# LVDS.net
KiCad netlist of a schematic drawn in Altium Designer
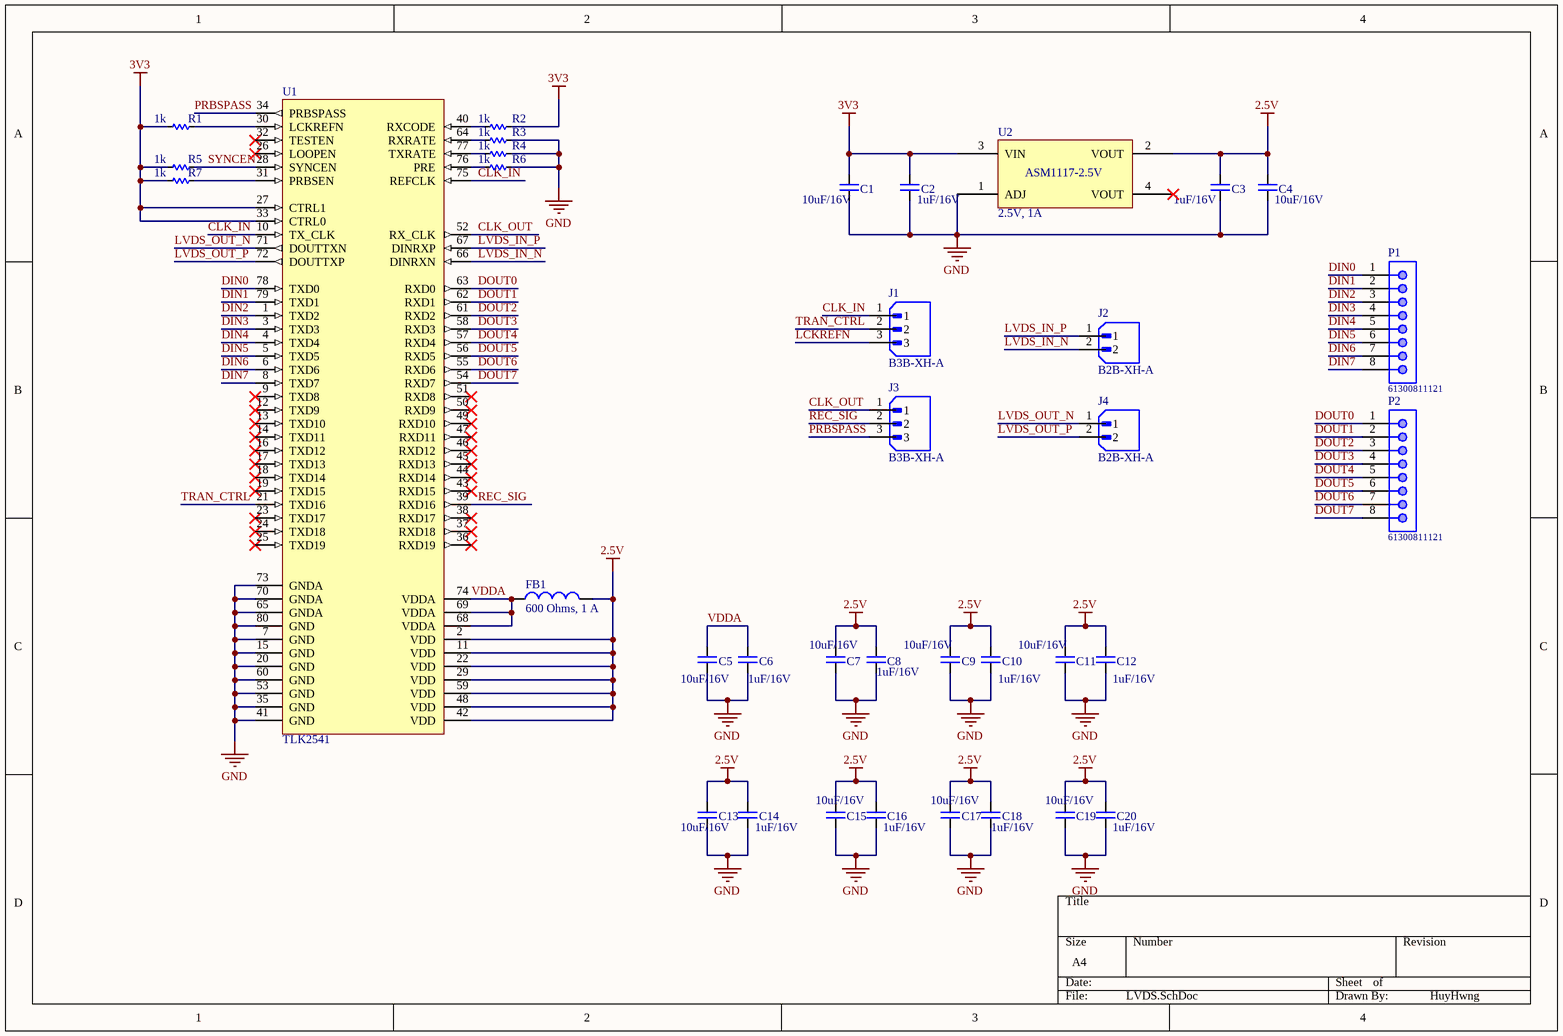
[diagram p0: LVDS.SchDoc]

(export (version "E")
  (design (tool "Eeschema 10.0.6"))
  (components
    (comp (ref "C1")
      (value "10uF/16V")
      (footprint "CAP_C_1608X80")
      (description "CAP_Chip")
      (libsource (lib "LABLIB") (part "CAP_SMD"))
    )
    (comp (ref "C2")
      (value "1uF/16V")
      (footprint "CAP_C_1608X80")
      (description "CAP_Chip")
      (libsource (lib "LABLIB") (part "CAP_SMD"))
    )
    (comp (ref "C3")
      (value "1uF/16V")
      (footprint "CAP_C_1608X80")
      (description "CAP_Chip")
      (libsource (lib "LABLIB") (part "CAP_SMD"))
    )
    (comp (ref "C4")
      (value "10uF/16V")
      (footprint "CAP_C_1608X80")
      (description "CAP_Chip")
      (libsource (lib "LABLIB") (part "CAP_SMD"))
    )
    (comp (ref "C5")
      (value "10uF/16V")
      (footprint "CAP_C_1608X80")
      (description "CAP_Chip")
      (libsource (lib "LABLIB") (part "CAP_SMD"))
    )
    (comp (ref "C6")
      (value "1uF/16V")
      (footprint "CAP_C_1608X80")
      (description "CAP_Chip")
      (libsource (lib "LABLIB") (part "CAP_SMD"))
    )
    (comp (ref "C7")
      (value "10uF/16V")
      (footprint "CAP_C_1608X80")
      (description "CAP_Chip")
      (libsource (lib "LABLIB") (part "CAP_SMD"))
    )
    (comp (ref "C8")
      (value "1uF/16V")
      (footprint "CAP_C_1608X80")
      (description "CAP_Chip")
      (libsource (lib "LABLIB") (part "CAP_SMD"))
    )
    (comp (ref "C9")
      (value "10uF/16V")
      (footprint "CAP_C_1608X80")
      (description "CAP_Chip")
      (libsource (lib "LABLIB") (part "CAP_SMD"))
    )
    (comp (ref "C10")
      (value "1uF/16V")
      (footprint "CAP_C_1608X80")
      (description "CAP_Chip")
      (libsource (lib "LABLIB") (part "CAP_SMD"))
    )
    (comp (ref "C11")
      (value "10uF/16V")
      (footprint "CAP_C_1608X80")
      (description "CAP_Chip")
      (libsource (lib "LABLIB") (part "CAP_SMD"))
    )
    (comp (ref "C12")
      (value "1uF/16V")
      (footprint "CAP_C_1608X80")
      (description "CAP_Chip")
      (libsource (lib "LABLIB") (part "CAP_SMD"))
    )
    (comp (ref "C13")
      (value "10uF/16V")
      (footprint "CAP_C_1608X80")
      (description "CAP_Chip")
      (libsource (lib "LABLIB") (part "CAP_SMD"))
    )
    (comp (ref "C14")
      (value "1uF/16V")
      (footprint "CAP_C_1608X80")
      (description "CAP_Chip")
      (libsource (lib "LABLIB") (part "CAP_SMD"))
    )
    (comp (ref "C15")
      (value "10uF/16V")
      (footprint "CAP_C_1608X80")
      (description "CAP_Chip")
      (libsource (lib "LABLIB") (part "CAP_SMD"))
    )
    (comp (ref "C16")
      (value "1uF/16V")
      (footprint "CAP_C_1608X80")
      (description "CAP_Chip")
      (libsource (lib "LABLIB") (part "CAP_SMD"))
    )
    (comp (ref "C17")
      (value "10uF/16V")
      (footprint "CAP_C_1608X80")
      (description "CAP_Chip")
      (libsource (lib "LABLIB") (part "CAP_SMD"))
    )
    (comp (ref "C18")
      (value "1uF/16V")
      (footprint "CAP_C_1608X80")
      (description "CAP_Chip")
      (libsource (lib "LABLIB") (part "CAP_SMD"))
    )
    (comp (ref "C19")
      (value "10uF/16V")
      (footprint "CAP_C_1608X80")
      (description "CAP_Chip")
      (libsource (lib "LABLIB") (part "CAP_SMD"))
    )
    (comp (ref "C20")
      (value "1uF/16V")
      (footprint "CAP_C_1608X80")
      (description "CAP_Chip")
      (libsource (lib "LABLIB") (part "CAP_SMD"))
    )
    (comp (ref "FB1")
      (value "600 Ohms, 1 A")
      (footprint "FER_0603")
      (description "Ferrite, 0603, 600 Ohms, 1 A")
      (fields (field (name "TOLERANCE") "+/-25%"))
      (libsource (lib "Altium_Ferrite_Bead") (part "03060360110225"))
    )
    (comp (ref "J1")
      (value "B3B-XH-A")
      (footprint "JST_B3B-XH-A")
      (description "Connector Header Through Hole 3 position 0.098 (2.50mm)")
      (fields (field (name "MF") "JST Sales"))
      (libsource (lib "B3B-XH-A") (part "B3B-XH-A"))
    )
    (comp (ref "J2")
      (value "B2B-XH-A")
      (footprint "JST_B2B-XH-A")
      (fields (field (name "MF") "{'manufacturer': u'JST Sales America Inc.'}"))
      (libsource (lib "B2B-XH-A") (part "B2B-XH-A"))
    )
    (comp (ref "J3")
      (value "B3B-XH-A")
      (footprint "JST_B3B-XH-A")
      (description "Connector Header Through Hole 3 position 0.098 (2.50mm)")
      (fields (field (name "MF") "JST Sales"))
      (libsource (lib "B3B-XH-A") (part "B3B-XH-A"))
    )
    (comp (ref "J4")
      (value "B2B-XH-A")
      (footprint "JST_B2B-XH-A")
      (fields (field (name "MF") "{'manufacturer': u'JST Sales America Inc.'}"))
      (libsource (lib "B2B-XH-A") (part "B2B-XH-A"))
    )
    (comp (ref "P1")
      (value "61300811121")
      (footprint "61300811121")
      (description "WR-PHD Pin Header, THT, pitch 2.54mm, Single Row, Vertical, 8p")
      (fields (field (name "MANUFACTURER") "Wurth Elektronik"))
      (libsource (lib "Altium_Header") (part "61300811121"))
    )
    (comp (ref "P2")
      (value "61300811121")
      (footprint "61300811121")
      (description "WR-PHD Pin Header, THT, pitch 2.54mm, Single Row, Vertical, 8p")
      (fields (field (name "MANUFACTURER") "Wurth Elektronik"))
      (libsource (lib "Altium_Header") (part "61300811121"))
    )
    (comp (ref "R1")
      (value "1k")
      (footprint "RES_C_1608X60")
      (description "RES")
      (libsource (lib "LABLIB") (part "_RES_B_2"))
    )
    (comp (ref "R2")
      (value "1k")
      (footprint "RES_C_1608X60")
      (description "RES")
      (libsource (lib "LABLIB") (part "_RES_B_2"))
    )
    (comp (ref "R3")
      (value "1k")
      (footprint "RES_C_1608X60")
      (description "RES")
      (libsource (lib "LABLIB") (part "_RES_B_2"))
    )
    (comp (ref "R4")
      (value "1k")
      (footprint "RES_C_1608X60")
      (description "RES")
      (libsource (lib "LABLIB") (part "_RES_B_2"))
    )
    (comp (ref "R5")
      (value "1k")
      (footprint "RES_C_1608X60")
      (description "RES")
      (libsource (lib "LABLIB") (part "_RES_B_2"))
    )
    (comp (ref "R6")
      (value "1k")
      (footprint "RES_C_1608X60")
      (description "RES")
      (libsource (lib "LABLIB") (part "_RES_B_2"))
    )
    (comp (ref "R7")
      (value "1k")
      (footprint "RES_C_1608X60")
      (description "RES")
      (libsource (lib "LABLIB") (part "_RES_B_2"))
    )
    (comp (ref "U1")
      (value "TLK2541")
      (footprint "TLK2541")
      (description "1 TO2.6 GBPS TRANSCEIVER")
      (libsource (lib "3_HuyHung") (part "TLK2541"))
    )
    (comp (ref "U2")
      (value "2.5V, 1A")
      (footprint "AMS1117-2.5V SOT223")
      (description "AMS1117-2.5V, OUT 2.5V 1A.")
      (fields (field (name "MANUFACTURER") "AMS"))
      (libsource (lib "Altium_Power_Supply_IC") (part "AMS1117-2.5V"))
    )
  )
  (nets
    (net (code "1") (name "/CLK_IN") (class "Default")
      (node (ref "J1") (pin "1") (pinfunction "1_1") (pintype "passive"))
      (node (ref "U1") (pin "10") (pinfunction "TX_CLK_10") (pintype "input"))
      (node (ref "U1") (pin "75") (pinfunction "REFCLK_75") (pintype "input"))
    )
    (net (code "2") (name "/CLK_OUT") (class "Default")
      (node (ref "J3") (pin "1") (pinfunction "1_1") (pintype "passive"))
      (node (ref "U1") (pin "52") (pinfunction "RX_CLK_52") (pintype "output"))
    )
    (net (code "3") (name "/DIN0") (class "Default")
      (node (ref "P1") (pin "1") (pinfunction "1_1") (pintype "passive"))
      (node (ref "U1") (pin "78") (pinfunction "TXD0_78") (pintype "input"))
    )
    (net (code "4") (name "/DIN1") (class "Default")
      (node (ref "P1") (pin "2") (pinfunction "2_2") (pintype "passive"))
      (node (ref "U1") (pin "79") (pinfunction "TXD1_79") (pintype "input"))
    )
    (net (code "5") (name "/DIN2") (class "Default")
      (node (ref "P1") (pin "3") (pinfunction "3_3") (pintype "passive"))
      (node (ref "U1") (pin "1") (pinfunction "TXD2_1") (pintype "input"))
    )
    (net (code "6") (name "/DIN3") (class "Default")
      (node (ref "P1") (pin "4") (pinfunction "4_4") (pintype "passive"))
      (node (ref "U1") (pin "3") (pinfunction "TXD3_3") (pintype "input"))
    )
    (net (code "7") (name "/DIN4") (class "Default")
      (node (ref "P1") (pin "5") (pinfunction "5_5") (pintype "passive"))
      (node (ref "U1") (pin "4") (pinfunction "TXD4_4") (pintype "input"))
    )
    (net (code "8") (name "/DIN5") (class "Default")
      (node (ref "P1") (pin "6") (pinfunction "6_6") (pintype "passive"))
      (node (ref "U1") (pin "5") (pinfunction "TXD5_5") (pintype "input"))
    )
    (net (code "9") (name "/DIN6") (class "Default")
      (node (ref "P1") (pin "7") (pinfunction "7_7") (pintype "passive"))
      (node (ref "U1") (pin "6") (pinfunction "TXD6_6") (pintype "input"))
    )
    (net (code "10") (name "/DIN7") (class "Default")
      (node (ref "P1") (pin "8") (pinfunction "8_8") (pintype "passive"))
      (node (ref "U1") (pin "8") (pinfunction "TXD7_8") (pintype "input"))
    )
    (net (code "11") (name "/DOUT0") (class "Default")
      (node (ref "P2") (pin "1") (pinfunction "1_1") (pintype "passive"))
      (node (ref "U1") (pin "63") (pinfunction "RXD0_63") (pintype "output"))
    )
    (net (code "12") (name "/DOUT1") (class "Default")
      (node (ref "P2") (pin "2") (pinfunction "2_2") (pintype "passive"))
      (node (ref "U1") (pin "62") (pinfunction "RXD1_62") (pintype "output"))
    )
    (net (code "13") (name "/DOUT2") (class "Default")
      (node (ref "P2") (pin "3") (pinfunction "3_3") (pintype "passive"))
      (node (ref "U1") (pin "61") (pinfunction "RXD2_61") (pintype "output"))
    )
    (net (code "14") (name "/DOUT3") (class "Default")
      (node (ref "P2") (pin "4") (pinfunction "4_4") (pintype "passive"))
      (node (ref "U1") (pin "58") (pinfunction "RXD3_58") (pintype "output"))
    )
    (net (code "15") (name "/DOUT4") (class "Default")
      (node (ref "P2") (pin "5") (pinfunction "5_5") (pintype "passive"))
      (node (ref "U1") (pin "57") (pinfunction "RXD4_57") (pintype "output"))
    )
    (net (code "16") (name "/DOUT5") (class "Default")
      (node (ref "P2") (pin "6") (pinfunction "6_6") (pintype "passive"))
      (node (ref "U1") (pin "56") (pinfunction "RXD5_56") (pintype "output"))
    )
    (net (code "17") (name "/DOUT6") (class "Default")
      (node (ref "P2") (pin "7") (pinfunction "7_7") (pintype "passive"))
      (node (ref "U1") (pin "55") (pinfunction "RXD6_55") (pintype "output"))
    )
    (net (code "18") (name "/DOUT7") (class "Default")
      (node (ref "P2") (pin "8") (pinfunction "8_8") (pintype "passive"))
      (node (ref "U1") (pin "54") (pinfunction "RXD7_54") (pintype "output"))
    )
    (net (code "19") (name "/LCKREFN") (class "Default")
      (node (ref "J1") (pin "3") (pinfunction "3_3") (pintype "passive"))
    )
    (net (code "20") (name "/LVDS_IN_N") (class "Default")
      (node (ref "J2") (pin "2") (pinfunction "2_2") (pintype "passive"))
      (node (ref "U1") (pin "66") (pinfunction "DINRXN_66") (pintype "input"))
    )
    (net (code "21") (name "/LVDS_IN_P") (class "Default")
      (node (ref "J2") (pin "1") (pinfunction "1_1") (pintype "passive"))
      (node (ref "U1") (pin "67") (pinfunction "DINRXP_67") (pintype "input"))
    )
    (net (code "22") (name "/LVDS_OUT_N") (class "Default")
      (node (ref "J4") (pin "1") (pinfunction "1_1") (pintype "passive"))
      (node (ref "U1") (pin "71") (pinfunction "DOUTTXN_71") (pintype "output"))
    )
    (net (code "23") (name "/LVDS_OUT_P") (class "Default")
      (node (ref "J4") (pin "2") (pinfunction "2_2") (pintype "passive"))
      (node (ref "U1") (pin "72") (pinfunction "DOUTTXP_72") (pintype "output"))
    )
    (net (code "24") (name "/PRBSPASS") (class "Default")
      (node (ref "J3") (pin "3") (pinfunction "3_3") (pintype "passive"))
      (node (ref "U1") (pin "34") (pinfunction "PRBSPASS_34") (pintype "output"))
    )
    (net (code "25") (name "/REC_SIG") (class "Default")
      (node (ref "J3") (pin "2") (pinfunction "2_2") (pintype "passive"))
      (node (ref "U1") (pin "39") (pinfunction "RXD16_39") (pintype "output"))
    )
    (net (code "26") (name "/SYNCEN") (class "Default")
      (node (ref "R5") (pin "1") (pinfunction "1_1") (pintype "passive"))
      (node (ref "U1") (pin "28") (pinfunction "SYNCEN_28") (pintype "input"))
    )
    (net (code "27") (name "/TRAN_CTRL") (class "Default")
      (node (ref "J1") (pin "2") (pinfunction "2_2") (pintype "passive"))
      (node (ref "U1") (pin "21") (pinfunction "TXD16_21") (pintype "input"))
    )
    (net (code "28") (name "/VDDA") (class "Default")
      (node (ref "C5") (pin "2") (pinfunction "2_2") (pintype "passive"))
      (node (ref "C6") (pin "2") (pinfunction "2_2") (pintype "passive"))
      (node (ref "FB1") (pin "1") (pinfunction "1_1") (pintype "passive"))
      (node (ref "U1") (pin "68") (pinfunction "VDDA_68") (pintype "power_in"))
      (node (ref "U1") (pin "69") (pinfunction "VDDA_69") (pintype "power_in"))
      (node (ref "U1") (pin "74") (pinfunction "VDDA_74") (pintype "power_in"))
    )
    (net (code "29") (name "2.5V") (class "Default")
      (node (ref "C10") (pin "2") (pinfunction "2_2") (pintype "passive"))
      (node (ref "C11") (pin "2") (pinfunction "2_2") (pintype "passive"))
      (node (ref "C12") (pin "2") (pinfunction "2_2") (pintype "passive"))
      (node (ref "C13") (pin "2") (pinfunction "2_2") (pintype "passive"))
      (node (ref "C14") (pin "2") (pinfunction "2_2") (pintype "passive"))
      (node (ref "C15") (pin "2") (pinfunction "2_2") (pintype "passive"))
      (node (ref "C16") (pin "2") (pinfunction "2_2") (pintype "passive"))
      (node (ref "C17") (pin "2") (pinfunction "2_2") (pintype "passive"))
      (node (ref "C18") (pin "2") (pinfunction "2_2") (pintype "passive"))
      (node (ref "C19") (pin "2") (pinfunction "2_2") (pintype "passive"))
      (node (ref "C20") (pin "2") (pinfunction "2_2") (pintype "passive"))
      (node (ref "C3") (pin "2") (pinfunction "2_2") (pintype "passive"))
      (node (ref "C4") (pin "2") (pinfunction "2_2") (pintype "passive"))
      (node (ref "C7") (pin "2") (pinfunction "2_2") (pintype "passive"))
      (node (ref "C8") (pin "2") (pinfunction "2_2") (pintype "passive"))
      (node (ref "C9") (pin "2") (pinfunction "2_2") (pintype "passive"))
      (node (ref "FB1") (pin "2") (pinfunction "2_2") (pintype "passive"))
      (node (ref "U1") (pin "11") (pinfunction "VDD_11") (pintype "power_in"))
      (node (ref "U1") (pin "2") (pinfunction "VDD_2") (pintype "power_in"))
      (node (ref "U1") (pin "22") (pinfunction "VDD_22") (pintype "power_in"))
      (node (ref "U1") (pin "29") (pinfunction "VDD_29") (pintype "power_in"))
      (node (ref "U1") (pin "42") (pinfunction "VDD_42") (pintype "power_in"))
      (node (ref "U1") (pin "48") (pinfunction "VDD_48") (pintype "power_in"))
      (node (ref "U1") (pin "59") (pinfunction "VDD_59") (pintype "power_in"))
      (node (ref "U2") (pin "2") (pinfunction "VOUT_2") (pintype "passive"))
    )
    (net (code "30") (name "3V3") (class "Default")
      (node (ref "C1") (pin "2") (pinfunction "2_2") (pintype "passive"))
      (node (ref "C2") (pin "2") (pinfunction "2_2") (pintype "passive"))
      (node (ref "R1") (pin "2") (pinfunction "2_2") (pintype "passive"))
      (node (ref "R2") (pin "1") (pinfunction "1_1") (pintype "passive"))
      (node (ref "R5") (pin "2") (pinfunction "2_2") (pintype "passive"))
      (node (ref "R7") (pin "2") (pinfunction "2_2") (pintype "passive"))
      (node (ref "U1") (pin "27") (pinfunction "CTRL1_27") (pintype "input"))
      (node (ref "U1") (pin "33") (pinfunction "CTRL0_33") (pintype "input"))
      (node (ref "U2") (pin "3") (pinfunction "VIN_3") (pintype "passive"))
    )
    (net (code "31") (name "GND") (class "Default")
      (node (ref "C1") (pin "1") (pinfunction "1_1") (pintype "passive"))
      (node (ref "C10") (pin "1") (pinfunction "1_1") (pintype "passive"))
      (node (ref "C11") (pin "1") (pinfunction "1_1") (pintype "passive"))
      (node (ref "C12") (pin "1") (pinfunction "1_1") (pintype "passive"))
      (node (ref "C13") (pin "1") (pinfunction "1_1") (pintype "passive"))
      (node (ref "C14") (pin "1") (pinfunction "1_1") (pintype "passive"))
      (node (ref "C15") (pin "1") (pinfunction "1_1") (pintype "passive"))
      (node (ref "C16") (pin "1") (pinfunction "1_1") (pintype "passive"))
      (node (ref "C17") (pin "1") (pinfunction "1_1") (pintype "passive"))
      (node (ref "C18") (pin "1") (pinfunction "1_1") (pintype "passive"))
      (node (ref "C19") (pin "1") (pinfunction "1_1") (pintype "passive"))
      (node (ref "C2") (pin "1") (pinfunction "1_1") (pintype "passive"))
      (node (ref "C20") (pin "1") (pinfunction "1_1") (pintype "passive"))
      (node (ref "C3") (pin "1") (pinfunction "1_1") (pintype "passive"))
      (node (ref "C4") (pin "1") (pinfunction "1_1") (pintype "passive"))
      (node (ref "C5") (pin "1") (pinfunction "1_1") (pintype "passive"))
      (node (ref "C6") (pin "1") (pinfunction "1_1") (pintype "passive"))
      (node (ref "C7") (pin "1") (pinfunction "1_1") (pintype "passive"))
      (node (ref "C8") (pin "1") (pinfunction "1_1") (pintype "passive"))
      (node (ref "C9") (pin "1") (pinfunction "1_1") (pintype "passive"))
      (node (ref "R3") (pin "1") (pinfunction "1_1") (pintype "passive"))
      (node (ref "R4") (pin "1") (pinfunction "1_1") (pintype "passive"))
      (node (ref "R6") (pin "1") (pinfunction "1_1") (pintype "passive"))
      (node (ref "U1") (pin "15") (pinfunction "GND_15") (pintype "power_in"))
      (node (ref "U1") (pin "20") (pinfunction "GND_20") (pintype "power_in"))
      (node (ref "U1") (pin "35") (pinfunction "GND_35") (pintype "power_in"))
      (node (ref "U1") (pin "41") (pinfunction "GND_41") (pintype "power_in"))
      (node (ref "U1") (pin "53") (pinfunction "GND_53") (pintype "power_in"))
      (node (ref "U1") (pin "60") (pinfunction "GND_60") (pintype "power_in"))
      (node (ref "U1") (pin "65") (pinfunction "GNDA_65") (pintype "power_in"))
      (node (ref "U1") (pin "7") (pinfunction "GND_7") (pintype "power_in"))
      (node (ref "U1") (pin "70") (pinfunction "GNDA_70") (pintype "power_in"))
      (node (ref "U1") (pin "73") (pinfunction "GNDA_73") (pintype "power_in"))
      (node (ref "U1") (pin "80") (pinfunction "GND_80") (pintype "power_in"))
      (node (ref "U2") (pin "1") (pinfunction "ADJ_1") (pintype "power_in"))
    )
    (net (code "32") (name "Net-(U1-LCKREFN)") (class "Default")
      (node (ref "R1") (pin "1") (pinfunction "1_1") (pintype "passive"))
      (node (ref "U1") (pin "30") (pinfunction "LCKREFN_30") (pintype "input"))
    )
    (net (code "33") (name "Net-(U1-PRBSEN)") (class "Default")
      (node (ref "R7") (pin "1") (pinfunction "1_1") (pintype "passive"))
      (node (ref "U1") (pin "31") (pinfunction "PRBSEN_31") (pintype "input"))
    )
    (net (code "34") (name "Net-(U1-PRE)") (class "Default")
      (node (ref "R6") (pin "2") (pinfunction "2_2") (pintype "passive"))
      (node (ref "U1") (pin "76") (pinfunction "PRE_76") (pintype "input"))
    )
    (net (code "35") (name "Net-(U1-RXCODE)") (class "Default")
      (node (ref "R2") (pin "2") (pinfunction "2_2") (pintype "passive"))
      (node (ref "U1") (pin "40") (pinfunction "RXCODE_40") (pintype "input"))
    )
    (net (code "36") (name "Net-(U1-RXRATE)") (class "Default")
      (node (ref "R3") (pin "2") (pinfunction "2_2") (pintype "passive"))
      (node (ref "U1") (pin "64") (pinfunction "RXRATE_64") (pintype "input"))
    )
    (net (code "37") (name "Net-(U1-TXRATE)") (class "Default")
      (node (ref "R4") (pin "2") (pinfunction "2_2") (pintype "passive"))
      (node (ref "U1") (pin "77") (pinfunction "TXRATE_77") (pintype "input"))
    )
    (net (code "38") (name "unconnected-(U1-LOOPEN-Pad26)") (class "Default")
      (node (ref "U1") (pin "26") (pinfunction "LOOPEN_26") (pintype "input+no_connect"))
    )
    (net (code "39") (name "unconnected-(U1-RXD8-Pad51)") (class "Default")
      (node (ref "U1") (pin "51") (pinfunction "RXD8_51") (pintype "output+no_connect"))
    )
    (net (code "40") (name "unconnected-(U1-RXD9-Pad50)") (class "Default")
      (node (ref "U1") (pin "50") (pinfunction "RXD9_50") (pintype "output+no_connect"))
    )
    (net (code "41") (name "unconnected-(U1-RXD10-Pad49)") (class "Default")
      (node (ref "U1") (pin "49") (pinfunction "RXD10_49") (pintype "output+no_connect"))
    )
    (net (code "42") (name "unconnected-(U1-RXD11-Pad47)") (class "Default")
      (node (ref "U1") (pin "47") (pinfunction "RXD11_47") (pintype "output+no_connect"))
    )
    (net (code "43") (name "unconnected-(U1-RXD12-Pad46)") (class "Default")
      (node (ref "U1") (pin "46") (pinfunction "RXD12_46") (pintype "output+no_connect"))
    )
    (net (code "44") (name "unconnected-(U1-RXD13-Pad45)") (class "Default")
      (node (ref "U1") (pin "45") (pinfunction "RXD13_45") (pintype "output+no_connect"))
    )
    (net (code "45") (name "unconnected-(U1-RXD14-Pad44)") (class "Default")
      (node (ref "U1") (pin "44") (pinfunction "RXD14_44") (pintype "output+no_connect"))
    )
    (net (code "46") (name "unconnected-(U1-RXD15-Pad43)") (class "Default")
      (node (ref "U1") (pin "43") (pinfunction "RXD15_43") (pintype "output+no_connect"))
    )
    (net (code "47") (name "unconnected-(U1-RXD17-Pad38)") (class "Default")
      (node (ref "U1") (pin "38") (pinfunction "RXD17_38") (pintype "output+no_connect"))
    )
    (net (code "48") (name "unconnected-(U1-RXD18-Pad37)") (class "Default")
      (node (ref "U1") (pin "37") (pinfunction "RXD18_37") (pintype "output+no_connect"))
    )
    (net (code "49") (name "unconnected-(U1-RXD19-Pad36)") (class "Default")
      (node (ref "U1") (pin "36") (pinfunction "RXD19_36") (pintype "output+no_connect"))
    )
    (net (code "50") (name "unconnected-(U1-TESTEN-Pad32)") (class "Default")
      (node (ref "U1") (pin "32") (pinfunction "TESTEN_32") (pintype "input+no_connect"))
    )
    (net (code "51") (name "unconnected-(U1-TXD8-Pad9)") (class "Default")
      (node (ref "U1") (pin "9") (pinfunction "TXD8_9") (pintype "input+no_connect"))
    )
    (net (code "52") (name "unconnected-(U1-TXD9-Pad12)") (class "Default")
      (node (ref "U1") (pin "12") (pinfunction "TXD9_12") (pintype "input+no_connect"))
    )
    (net (code "53") (name "unconnected-(U1-TXD10-Pad13)") (class "Default")
      (node (ref "U1") (pin "13") (pinfunction "TXD10_13") (pintype "input+no_connect"))
    )
    (net (code "54") (name "unconnected-(U1-TXD11-Pad14)") (class "Default")
      (node (ref "U1") (pin "14") (pinfunction "TXD11_14") (pintype "input+no_connect"))
    )
    (net (code "55") (name "unconnected-(U1-TXD12-Pad16)") (class "Default")
      (node (ref "U1") (pin "16") (pinfunction "TXD12_16") (pintype "input+no_connect"))
    )
    (net (code "56") (name "unconnected-(U1-TXD13-Pad17)") (class "Default")
      (node (ref "U1") (pin "17") (pinfunction "TXD13_17") (pintype "input+no_connect"))
    )
    (net (code "57") (name "unconnected-(U1-TXD14-Pad18)") (class "Default")
      (node (ref "U1") (pin "18") (pinfunction "TXD14_18") (pintype "input+no_connect"))
    )
    (net (code "58") (name "unconnected-(U1-TXD15-Pad19)") (class "Default")
      (node (ref "U1") (pin "19") (pinfunction "TXD15_19") (pintype "input+no_connect"))
    )
    (net (code "59") (name "unconnected-(U1-TXD17-Pad23)") (class "Default")
      (node (ref "U1") (pin "23") (pinfunction "TXD17_23") (pintype "input+no_connect"))
    )
    (net (code "60") (name "unconnected-(U1-TXD18-Pad24)") (class "Default")
      (node (ref "U1") (pin "24") (pinfunction "TXD18_24") (pintype "input+no_connect"))
    )
    (net (code "61") (name "unconnected-(U1-TXD19-Pad25)") (class "Default")
      (node (ref "U1") (pin "25") (pinfunction "TXD19_25") (pintype "input+no_connect"))
    )
    (net (code "62") (name "unconnected-(U2-VOUT-Pad4)") (class "Default")
      (node (ref "U2") (pin "4") (pinfunction "VOUT_4") (pintype "power_in+no_connect"))
    )
  )
)
